# K22Power.net
KiCad netlist of a schematic drawn in Altium Designer
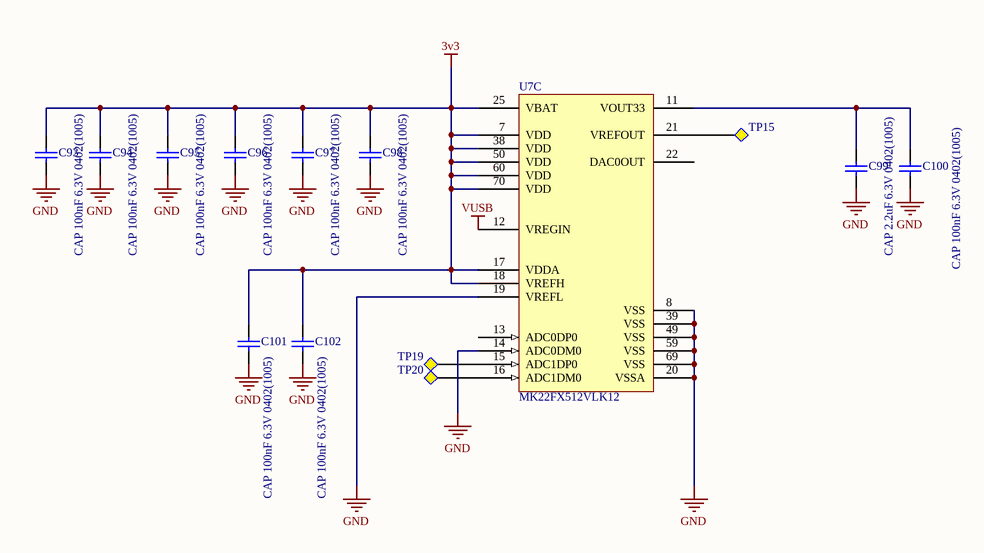
[diagram p0: K22Power.SchDoc]

(export (version "E")
  (design (tool "Eeschema 10.0.6"))
  (components
    (comp (ref "C93")
      (value "CAP 100nF 6.3V 0402(1005)")
      (footprint "CAPC0402(1005)60_M")
      (description "CAP 100nF 6.3V ±20% 0402 (1005 Metric) Thickness 0.6mm SMD")
      (fields (field (name "TOLERANCE") "Â±20%"))
      (libsource (lib "Altium Content Vault") (part "CAP"))
    )
    (comp (ref "C94")
      (value "CAP 100nF 6.3V 0402(1005)")
      (footprint "CAPC0402(1005)60_M")
      (description "CAP 100nF 6.3V ±20% 0402 (1005 Metric) Thickness 0.6mm SMD")
      (fields (field (name "TOLERANCE") "Â±20%"))
      (libsource (lib "Altium Content Vault") (part "CAP"))
    )
    (comp (ref "C95")
      (value "CAP 100nF 6.3V 0402(1005)")
      (footprint "CAPC0402(1005)60_M")
      (description "CAP 100nF 6.3V ±20% 0402 (1005 Metric) Thickness 0.6mm SMD")
      (fields (field (name "TOLERANCE") "Â±20%"))
      (libsource (lib "Altium Content Vault") (part "CAP"))
    )
    (comp (ref "C96")
      (value "CAP 100nF 6.3V 0402(1005)")
      (footprint "CAPC0402(1005)60_M")
      (description "CAP 100nF 6.3V ±20% 0402 (1005 Metric) Thickness 0.6mm SMD")
      (fields (field (name "TOLERANCE") "Â±20%"))
      (libsource (lib "Altium Content Vault") (part "CAP"))
    )
    (comp (ref "C97")
      (value "CAP 100nF 6.3V 0402(1005)")
      (footprint "CAPC0402(1005)60_M")
      (description "CAP 100nF 6.3V ±20% 0402 (1005 Metric) Thickness 0.6mm SMD")
      (fields (field (name "TOLERANCE") "Â±20%"))
      (libsource (lib "Altium Content Vault") (part "CAP"))
    )
    (comp (ref "C98")
      (value "CAP 100nF 6.3V 0402(1005)")
      (footprint "CAPC0402(1005)60_M")
      (description "CAP 100nF 6.3V ±20% 0402 (1005 Metric) Thickness 0.6mm SMD")
      (fields (field (name "TOLERANCE") "Â±20%"))
      (libsource (lib "Altium Content Vault") (part "CAP"))
    )
    (comp (ref "C99")
      (value "CAP 2.2uF 6.3V 0402(1005)")
      (footprint "CAPC0402(1005)60_L")
      (description "CAP 2.2uF 6.3V ±20% 0402 (1005 Metric) Thickness 0.6mm SMD")
      (fields (field (name "TOLERANCE") "Â±20%"))
      (libsource (lib "Altium Content Vault") (part "CAP"))
    )
    (comp (ref "C100")
      (value "CAP 100nF 6.3V 0402(1005)")
      (footprint "CAPC0402(1005)60_M")
      (description "CAP 100nF 6.3V ±20% 0402 (1005 Metric) Thickness 0.6mm SMD")
      (fields (field (name "TOLERANCE") "Â±20%"))
      (libsource (lib "Altium Content Vault") (part "CAP"))
    )
    (comp (ref "C101")
      (value "CAP 100nF 6.3V 0402(1005)")
      (footprint "CAPC0402(1005)60_M")
      (description "CAP 100nF 6.3V ±20% 0402 (1005 Metric) Thickness 0.6mm SMD")
      (fields (field (name "TOLERANCE") "Â±20%"))
      (libsource (lib "Altium Content Vault") (part "CAP"))
    )
    (comp (ref "C102")
      (value "CAP 100nF 6.3V 0402(1005)")
      (footprint "CAPC0402(1005)60_M")
      (description "CAP 100nF 6.3V ±20% 0402 (1005 Metric) Thickness 0.6mm SMD")
      (fields (field (name "TOLERANCE") "Â±20%"))
      (libsource (lib "Altium Content Vault") (part "CAP"))
    )
    (comp (ref "TP15") (value "Test Point") (footprint "TP") (libsource (lib "parts") (part "TP")))
    (comp (ref "TP19") (value "Test Point") (footprint "TP") (libsource (lib "parts") (part "TP")))
    (comp (ref "TP20") (value "Test Point") (footprint "TP") (libsource (lib "parts") (part "TP")))
    (comp (ref "U7")
      (value "MK22FX512VLK12")
      (footprint "TSQFP50P1400X1400X160-80N")
      (libsource (lib "parts") (part "MK22FX512VLK12"))
    )
  )
  (nets
    (net (code "1") (name "3v3") (class "Default")
      (node (ref "C101") (pin "2") (pinfunction "2_2") (pintype "passive"))
      (node (ref "C102") (pin "2") (pinfunction "2_2") (pintype "passive"))
      (node (ref "C93") (pin "2") (pinfunction "2_2") (pintype "passive"))
      (node (ref "C94") (pin "2") (pinfunction "2_2") (pintype "passive"))
      (node (ref "C95") (pin "2") (pinfunction "2_2") (pintype "passive"))
      (node (ref "C96") (pin "2") (pinfunction "2_2") (pintype "passive"))
      (node (ref "C97") (pin "2") (pinfunction "2_2") (pintype "passive"))
      (node (ref "C98") (pin "2") (pinfunction "2_2") (pintype "passive"))
      (node (ref "U7") (pin "17") (pinfunction "VDDA_17") (pintype "power_in"))
      (node (ref "U7") (pin "18") (pinfunction "VREFH_18") (pintype "power_in"))
      (node (ref "U7") (pin "25") (pinfunction "VBAT_25") (pintype "power_in"))
      (node (ref "U7") (pin "38") (pinfunction "VDD_38") (pintype "power_in"))
      (node (ref "U7") (pin "50") (pinfunction "VDD_50") (pintype "power_in"))
      (node (ref "U7") (pin "60") (pinfunction "VDD_60") (pintype "power_in"))
      (node (ref "U7") (pin "7") (pinfunction "VDD_7") (pintype "power_in"))
      (node (ref "U7") (pin "70") (pinfunction "VDD_70") (pintype "power_in"))
    )
    (net (code "2") (name "GND") (class "Default")
      (node (ref "C100") (pin "1") (pinfunction "1_1") (pintype "passive"))
      (node (ref "C101") (pin "1") (pinfunction "1_1") (pintype "passive"))
      (node (ref "C102") (pin "1") (pinfunction "1_1") (pintype "passive"))
      (node (ref "C93") (pin "1") (pinfunction "1_1") (pintype "passive"))
      (node (ref "C94") (pin "1") (pinfunction "1_1") (pintype "passive"))
      (node (ref "C95") (pin "1") (pinfunction "1_1") (pintype "passive"))
      (node (ref "C96") (pin "1") (pinfunction "1_1") (pintype "passive"))
      (node (ref "C97") (pin "1") (pinfunction "1_1") (pintype "passive"))
      (node (ref "C98") (pin "1") (pinfunction "1_1") (pintype "passive"))
      (node (ref "C99") (pin "1") (pinfunction "1_1") (pintype "passive"))
      (node (ref "U7") (pin "14") (pinfunction "ADC0DM0_14") (pintype "input"))
      (node (ref "U7") (pin "19") (pinfunction "VREFL_19") (pintype "power_in"))
      (node (ref "U7") (pin "20") (pinfunction "VSSA_20") (pintype "power_in"))
      (node (ref "U7") (pin "39") (pinfunction "VSS_39") (pintype "power_in"))
      (node (ref "U7") (pin "49") (pinfunction "VSS_49") (pintype "power_in"))
      (node (ref "U7") (pin "59") (pinfunction "VSS_59") (pintype "power_in"))
      (node (ref "U7") (pin "69") (pinfunction "VSS_69") (pintype "power_in"))
      (node (ref "U7") (pin "8") (pinfunction "VSS_8") (pintype "power_in"))
    )
    (net (code "3") (name "Net-(U7C-ADC1DM0)") (class "Default")
      (node (ref "TP20") (pin "1") (pinfunction "1_1") (pintype "passive"))
      (node (ref "U7") (pin "16") (pinfunction "ADC1DM0_16") (pintype "input"))
    )
    (net (code "4") (name "Net-(U7C-ADC1DP0)") (class "Default")
      (node (ref "TP19") (pin "1") (pinfunction "1_1") (pintype "passive"))
      (node (ref "U7") (pin "15") (pinfunction "ADC1DP0_15") (pintype "input"))
    )
    (net (code "5") (name "Net-(U7C-VOUT33)") (class "Default")
      (node (ref "C100") (pin "2") (pinfunction "2_2") (pintype "passive"))
      (node (ref "C99") (pin "2") (pinfunction "2_2") (pintype "passive"))
      (node (ref "U7") (pin "11") (pinfunction "VOUT33_11") (pintype "power_in"))
    )
    (net (code "6") (name "Net-(U7C-VREFOUT)") (class "Default")
      (node (ref "TP15") (pin "1") (pinfunction "1_1") (pintype "passive"))
      (node (ref "U7") (pin "21") (pinfunction "VREFOUT_21") (pintype "power_in"))
    )
    (net (code "7") (name "VUSB") (class "Default")
      (node (ref "U7") (pin "12") (pinfunction "VREGIN_12") (pintype "power_in"))
    )
    (net (code "8") (name "unconnected-(U7C-ADC0DP0-Pad13)") (class "Default")
      (node (ref "U7") (pin "13") (pinfunction "ADC0DP0_13") (pintype "input"))
    )
    (net (code "9") (name "unconnected-(U7C-DAC0OUT-Pad22)") (class "Default")
      (node (ref "U7") (pin "22") (pinfunction "DAC0OUT_22") (pintype "power_in"))
    )
  )
)
